# USB.net
KiCad netlist of a schematic drawn in Altium Designer
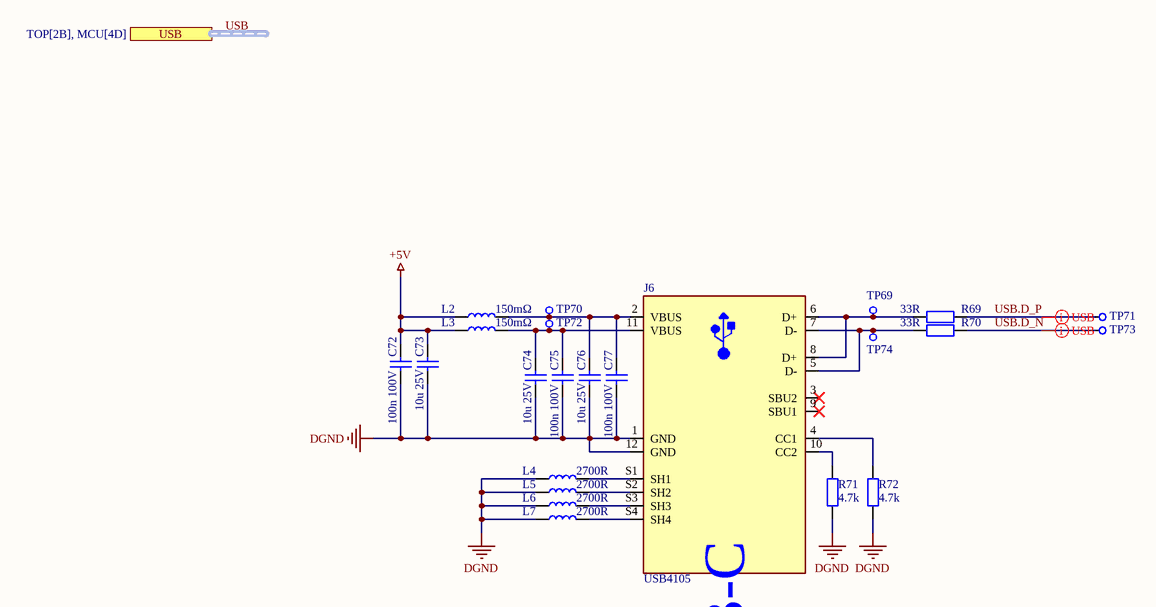
[diagram p0: USB.SchDoc]

(export (version "E")
  (design (tool "Eeschema 10.0.6"))
  (components
    (comp (ref "C72")
      (value "100n 100V")
      (footprint "FOOTPRINTS:CAPACITOR 0805")
      (description "Capacitor: ceramic; MLCC; 100nF; 100V; X7R; ±10%; SMD; 0805")
      (fields
        (field (name "MANUFACTURER") "YAGEO")
        (field (name "MANUFACTURER PART NUMBER") "CC0805KKX7R0BB104")
      )
      (libsource (lib "SYMBOLS") (part "Capacitor 100n 100V 10% X7R 0805"))
    )
    (comp (ref "C73")
      (value "10u 25V")
      (footprint "FOOTPRINTS:CAPACITOR 0805")
      (description "Capacitor: ceramic; MLCC; 10uF; 25V; X5R; ±10%; SMD; 0805")
      (fields
        (field (name "MANUFACTURER") "MURATA")
        (field (name "MANUFACTURER PART NUMBER") "GRM21BR61E106KA73K")
      )
      (libsource (lib "SYMBOLS") (part "Capacitor 10u 25V 10% X5R 0805"))
    )
    (comp (ref "C74")
      (value "10u 25V")
      (footprint "FOOTPRINTS:CAPACITOR 0805")
      (description "Capacitor: ceramic; MLCC; 10uF; 25V; X5R; ±10%; SMD; 0805")
      (fields
        (field (name "MANUFACTURER") "MURATA")
        (field (name "MANUFACTURER PART NUMBER") "GRM21BR61E106KA73K")
      )
      (libsource (lib "SYMBOLS") (part "Capacitor 10u 25V 10% X5R 0805"))
    )
    (comp (ref "C75")
      (value "100n 100V")
      (footprint "FOOTPRINTS:CAPACITOR 0805")
      (description "Capacitor: ceramic; MLCC; 100nF; 100V; X7R; ±10%; SMD; 0805")
      (fields
        (field (name "MANUFACTURER") "YAGEO")
        (field (name "MANUFACTURER PART NUMBER") "CC0805KKX7R0BB104")
      )
      (libsource (lib "SYMBOLS") (part "Capacitor 100n 100V 10% X7R 0805"))
    )
    (comp (ref "C76")
      (value "10u 25V")
      (footprint "FOOTPRINTS:CAPACITOR 0805")
      (description "Capacitor: ceramic; MLCC; 10uF; 25V; X5R; ±10%; SMD; 0805")
      (fields
        (field (name "MANUFACTURER") "MURATA")
        (field (name "MANUFACTURER PART NUMBER") "GRM21BR61E106KA73K")
      )
      (libsource (lib "SYMBOLS") (part "Capacitor 10u 25V 10% X5R 0805"))
    )
    (comp (ref "C77")
      (value "100n 100V")
      (footprint "FOOTPRINTS:CAPACITOR 0805")
      (description "Capacitor: ceramic; MLCC; 100nF; 100V; X7R; ±10%; SMD; 0805")
      (fields
        (field (name "MANUFACTURER") "YAGEO")
        (field (name "MANUFACTURER PART NUMBER") "CC0805KKX7R0BB104")
      )
      (libsource (lib "SYMBOLS") (part "Capacitor 100n 100V 10% X7R 0805"))
    )
    (comp (ref "J6")
      (value "USB4105")
      (footprint "FOOTPRINTS:MECHANICAL USB USB4105")
      (description "Socket; USB C; SMT; PIN: 16; horizontal; top board mount; USB 2.0")
      (fields (field (name "MANUFACTURER") "GCT") (field (name "MANUFACTURER PART NUMBER") "USB4105-GF-A"))
      (libsource (lib "SYMBOLS") (part "Mechanical USB-C Right Angle MUSBRM1C130"))
    )
    (comp (ref "L2")
      (value "150mΩ")
      (footprint "FOOTPRINTS:FERRITE 0805")
      (description "Inductor: ferrite; SMD; 0805; 2.2uH; 1A; 150mΩ; 2MHz; ±20%; -40÷125°C")
      (fields
        (field (name "MANUFACTURER") "TDK")
        (field (name "MANUFACTURER PART NUMBER") "MLP2012H2R2MT0S1")
      )
      (libsource (lib "SYMBOLS") (part "Inductor Ferrite Bead 150mΩ 0805 1A"))
    )
    (comp (ref "L3")
      (value "150mΩ")
      (footprint "FOOTPRINTS:FERRITE 0805")
      (description "Inductor: ferrite; SMD; 0805; 2.2uH; 1A; 150mΩ; 2MHz; ±20%; -40÷125°C")
      (fields
        (field (name "MANUFACTURER") "TDK")
        (field (name "MANUFACTURER PART NUMBER") "MLP2012H2R2MT0S1")
      )
      (libsource (lib "SYMBOLS") (part "Inductor Ferrite Bead 150mΩ 0805 1A"))
    )
    (comp (ref "L4")
      (value "2700R")
      (footprint "FOOTPRINTS:FERRITE 0805")
      (description "Ferrite: bead; 2700Ω; SMD; 200mA; 0805; -55÷125°C")
      (fields
        (field (name "MANUFACTURER") "MURATA")
        (field (name "MANUFACTURER PART NUMBER") "BLM21BD272SN1L")
      )
      (libsource (lib "SYMBOLS") (part "Inductor Ferrite Bead 2700Ω 0805 0.2A"))
    )
    (comp (ref "L5")
      (value "2700R")
      (footprint "FOOTPRINTS:FERRITE 0805")
      (description "Ferrite: bead; 2700Ω; SMD; 200mA; 0805; -55÷125°C")
      (fields
        (field (name "MANUFACTURER") "MURATA")
        (field (name "MANUFACTURER PART NUMBER") "BLM21BD272SN1L")
      )
      (libsource (lib "SYMBOLS") (part "Inductor Ferrite Bead 2700Ω 0805 0.2A"))
    )
    (comp (ref "L6")
      (value "2700R")
      (footprint "FOOTPRINTS:FERRITE 0805")
      (description "Ferrite: bead; 2700Ω; SMD; 200mA; 0805; -55÷125°C")
      (fields
        (field (name "MANUFACTURER") "MURATA")
        (field (name "MANUFACTURER PART NUMBER") "BLM21BD272SN1L")
      )
      (libsource (lib "SYMBOLS") (part "Inductor Ferrite Bead 2700Ω 0805 0.2A"))
    )
    (comp (ref "L7")
      (value "2700R")
      (footprint "FOOTPRINTS:FERRITE 0805")
      (description "Ferrite: bead; 2700Ω; SMD; 200mA; 0805; -55÷125°C")
      (fields
        (field (name "MANUFACTURER") "MURATA")
        (field (name "MANUFACTURER PART NUMBER") "BLM21BD272SN1L")
      )
      (libsource (lib "SYMBOLS") (part "Inductor Ferrite Bead 2700Ω 0805 0.2A"))
    )
    (comp (ref "R69")
      (value "33R")
      (footprint "FOOTPRINTS:RESISTOR 0805")
      (description "Resistor: thick film; SMD; 0805; 33Ω; 0.125W; ±1%; -55÷155°C")
      (fields
        (field (name "MANUFACTURER") "Yageo")
        (field (name "MANUFACTURER PART NUMBER") "RC0805FR-0733R")
      )
      (libsource (lib "SYMBOLS") (part "Resistor 33R 1% 1/8W 0805"))
    )
    (comp (ref "R70")
      (value "33R")
      (footprint "FOOTPRINTS:RESISTOR 0805")
      (description "Resistor: thick film; SMD; 0805; 33Ω; 0.125W; ±1%; -55÷155°C")
      (fields
        (field (name "MANUFACTURER") "Yageo")
        (field (name "MANUFACTURER PART NUMBER") "RC0805FR-0733R")
      )
      (libsource (lib "SYMBOLS") (part "Resistor 33R 1% 1/8W 0805"))
    )
    (comp (ref "R71")
      (value "4.7k")
      (footprint "FOOTPRINTS:RESISTOR 0805")
      (description "Resistor: thick film; SMD; 0805; 4.7kΩ; 0.125W; ±1%; -55÷155°C")
      (fields
        (field (name "MANUFACTURER") "Yageo")
        (field (name "MANUFACTURER PART NUMBER") "RC0805FR-074K7")
      )
      (libsource (lib "SYMBOLS") (part "Resistor 4.7k 1% 1/8W 0805"))
    )
    (comp (ref "R72")
      (value "4.7k")
      (footprint "FOOTPRINTS:RESISTOR 0805")
      (description "Resistor: thick film; SMD; 0805; 4.7kΩ; 0.125W; ±1%; -55÷155°C")
      (fields
        (field (name "MANUFACTURER") "Yageo")
        (field (name "MANUFACTURER PART NUMBER") "RC0805FR-074K7")
      )
      (libsource (lib "SYMBOLS") (part "Resistor 4.7k 1% 1/8W 0805"))
    )
    (comp (ref "TP69")
      (value "1mm")
      (footprint "FOOTPRINTS:TEST POINT 1MM")
      (description "Tesp Point 1mm")
      (libsource (lib "SYMBOLS") (part "Mechanical Test Point 1mm"))
    )
    (comp (ref "TP70")
      (value "1mm")
      (footprint "FOOTPRINTS:TEST POINT 1MM")
      (description "Tesp Point 1mm")
      (libsource (lib "SYMBOLS") (part "Mechanical Test Point 1mm"))
    )
    (comp (ref "TP71")
      (value "1mm")
      (footprint "FOOTPRINTS:TEST POINT 1MM")
      (description "Tesp Point 1mm")
      (libsource (lib "SYMBOLS") (part "Mechanical Test Point 1mm"))
    )
    (comp (ref "TP72")
      (value "1mm")
      (footprint "FOOTPRINTS:TEST POINT 1MM")
      (description "Tesp Point 1mm")
      (libsource (lib "SYMBOLS") (part "Mechanical Test Point 1mm"))
    )
    (comp (ref "TP73")
      (value "1mm")
      (footprint "FOOTPRINTS:TEST POINT 1MM")
      (description "Tesp Point 1mm")
      (libsource (lib "SYMBOLS") (part "Mechanical Test Point 1mm"))
    )
    (comp (ref "TP74")
      (value "1mm")
      (footprint "FOOTPRINTS:TEST POINT 1MM")
      (description "Tesp Point 1mm")
      (libsource (lib "SYMBOLS") (part "Mechanical Test Point 1mm"))
    )
  )
  (nets
    (net (code "2") (name "+5V") (class "Default")
      (node (ref "C72") (pin "2") (pinfunction "2_2") (pintype "passive"))
      (node (ref "C73") (pin "2") (pinfunction "2_2") (pintype "passive"))
      (node (ref "L2") (pin "1") (pinfunction "1_1") (pintype "passive"))
      (node (ref "L3") (pin "1") (pinfunction "1_1") (pintype "passive"))
    )
    (net (code "3") (name "/USB.D_N") (class "Default")
      (node (ref "R70") (pin "2") (pinfunction "2_2") (pintype "passive"))
      (node (ref "TP73") (pin "1") (pinfunction "1_1") (pintype "passive"))
    )
    (net (code "4") (name "/USB.D_P") (class "Default")
      (node (ref "R69") (pin "2") (pinfunction "2_2") (pintype "passive"))
      (node (ref "TP71") (pin "1") (pinfunction "1_1") (pintype "passive"))
    )
    (net (code "6") (name "DGND") (class "Default")
      (node (ref "C72") (pin "1") (pinfunction "1_1") (pintype "passive"))
      (node (ref "C73") (pin "1") (pinfunction "1_1") (pintype "passive"))
      (node (ref "C74") (pin "1") (pinfunction "1_1") (pintype "passive"))
      (node (ref "C75") (pin "1") (pinfunction "1_1") (pintype "passive"))
      (node (ref "C76") (pin "1") (pinfunction "1_1") (pintype "passive"))
      (node (ref "C77") (pin "1") (pinfunction "1_1") (pintype "passive"))
      (node (ref "J6") (pin "1") (pinfunction "GND_1") (pintype "passive"))
      (node (ref "J6") (pin "12") (pinfunction "GND_12") (pintype "passive"))
      (node (ref "L4") (pin "1") (pinfunction "1_1") (pintype "passive"))
      (node (ref "L5") (pin "1") (pinfunction "1_1") (pintype "passive"))
      (node (ref "L6") (pin "1") (pinfunction "1_1") (pintype "passive"))
      (node (ref "L7") (pin "1") (pinfunction "1_1") (pintype "passive"))
      (node (ref "R71") (pin "1") (pinfunction "1_1") (pintype "passive"))
      (node (ref "R72") (pin "1") (pinfunction "1_1") (pintype "passive"))
    )
    (net (code "7") (name "Net-(C74-Pad2)") (class "Default")
      (node (ref "C74") (pin "2") (pinfunction "2_2") (pintype "passive"))
      (node (ref "C75") (pin "2") (pinfunction "2_2") (pintype "passive"))
      (node (ref "J6") (pin "11") (pinfunction "VBUS_11") (pintype "passive"))
      (node (ref "L3") (pin "2") (pinfunction "2_2") (pintype "passive"))
      (node (ref "TP72") (pin "1") (pinfunction "1_1") (pintype "passive"))
    )
    (net (code "8") (name "Net-(C76-Pad2)") (class "Default")
      (node (ref "C76") (pin "2") (pinfunction "2_2") (pintype "passive"))
      (node (ref "C77") (pin "2") (pinfunction "2_2") (pintype "passive"))
      (node (ref "J6") (pin "2") (pinfunction "VBUS_2") (pintype "passive"))
      (node (ref "L2") (pin "2") (pinfunction "2_2") (pintype "passive"))
      (node (ref "TP70") (pin "1") (pinfunction "1_1") (pintype "passive"))
    )
    (net (code "9") (name "Net-(J6-CC1)") (class "Default")
      (node (ref "J6") (pin "4") (pinfunction "CC1_4") (pintype "passive"))
      (node (ref "R72") (pin "2") (pinfunction "2_2") (pintype "passive"))
    )
    (net (code "10") (name "Net-(J6-CC2)") (class "Default")
      (node (ref "J6") (pin "10") (pinfunction "CC2_10") (pintype "passive"))
      (node (ref "R71") (pin "2") (pinfunction "2_2") (pintype "passive"))
    )
    (net (code "11") (name "Net-(J6-D+-Pad6)") (class "Default")
      (node (ref "J6") (pin "6") (pinfunction "D+_6") (pintype "passive"))
      (node (ref "J6") (pin "8") (pinfunction "D+_8") (pintype "passive"))
      (node (ref "R69") (pin "1") (pinfunction "1_1") (pintype "passive"))
      (node (ref "TP69") (pin "1") (pinfunction "1_1") (pintype "passive"))
    )
    (net (code "12") (name "Net-(J6-D--Pad5)") (class "Default")
      (node (ref "J6") (pin "5") (pinfunction "D-_5") (pintype "passive"))
      (node (ref "J6") (pin "7") (pinfunction "D-_7") (pintype "passive"))
      (node (ref "R70") (pin "1") (pinfunction "1_1") (pintype "passive"))
      (node (ref "TP74") (pin "1") (pinfunction "1_1") (pintype "passive"))
    )
    (net (code "13") (name "Net-(J6-SH1)") (class "Default")
      (node (ref "J6") (pin "S1") (pinfunction "SH1_S1") (pintype "passive"))
      (node (ref "L4") (pin "2") (pinfunction "2_2") (pintype "passive"))
    )
    (net (code "14") (name "Net-(J6-SH2)") (class "Default")
      (node (ref "J6") (pin "S2") (pinfunction "SH2_S2") (pintype "passive"))
      (node (ref "L5") (pin "2") (pinfunction "2_2") (pintype "passive"))
    )
    (net (code "15") (name "Net-(J6-SH3)") (class "Default")
      (node (ref "J6") (pin "S3") (pinfunction "SH3_S3") (pintype "passive"))
      (node (ref "L6") (pin "2") (pinfunction "2_2") (pintype "passive"))
    )
    (net (code "16") (name "Net-(J6-SH4)") (class "Default")
      (node (ref "J6") (pin "S4") (pinfunction "SH4_S4") (pintype "passive"))
      (node (ref "L7") (pin "2") (pinfunction "2_2") (pintype "passive"))
    )
    (net (code "17") (name "unconnected-(J6-SBU1-Pad9)") (class "Default")
      (node (ref "J6") (pin "9") (pinfunction "SBU1_9") (pintype "passive+no_connect"))
    )
    (net (code "18") (name "unconnected-(J6-SBU2-Pad3)") (class "Default")
      (node (ref "J6") (pin "3") (pinfunction "SBU2_3") (pintype "passive+no_connect"))
    )
  )
)
